# FRAM_with_level_converter_integrated.net
KiCad netlist of a schematic drawn in EAGLE
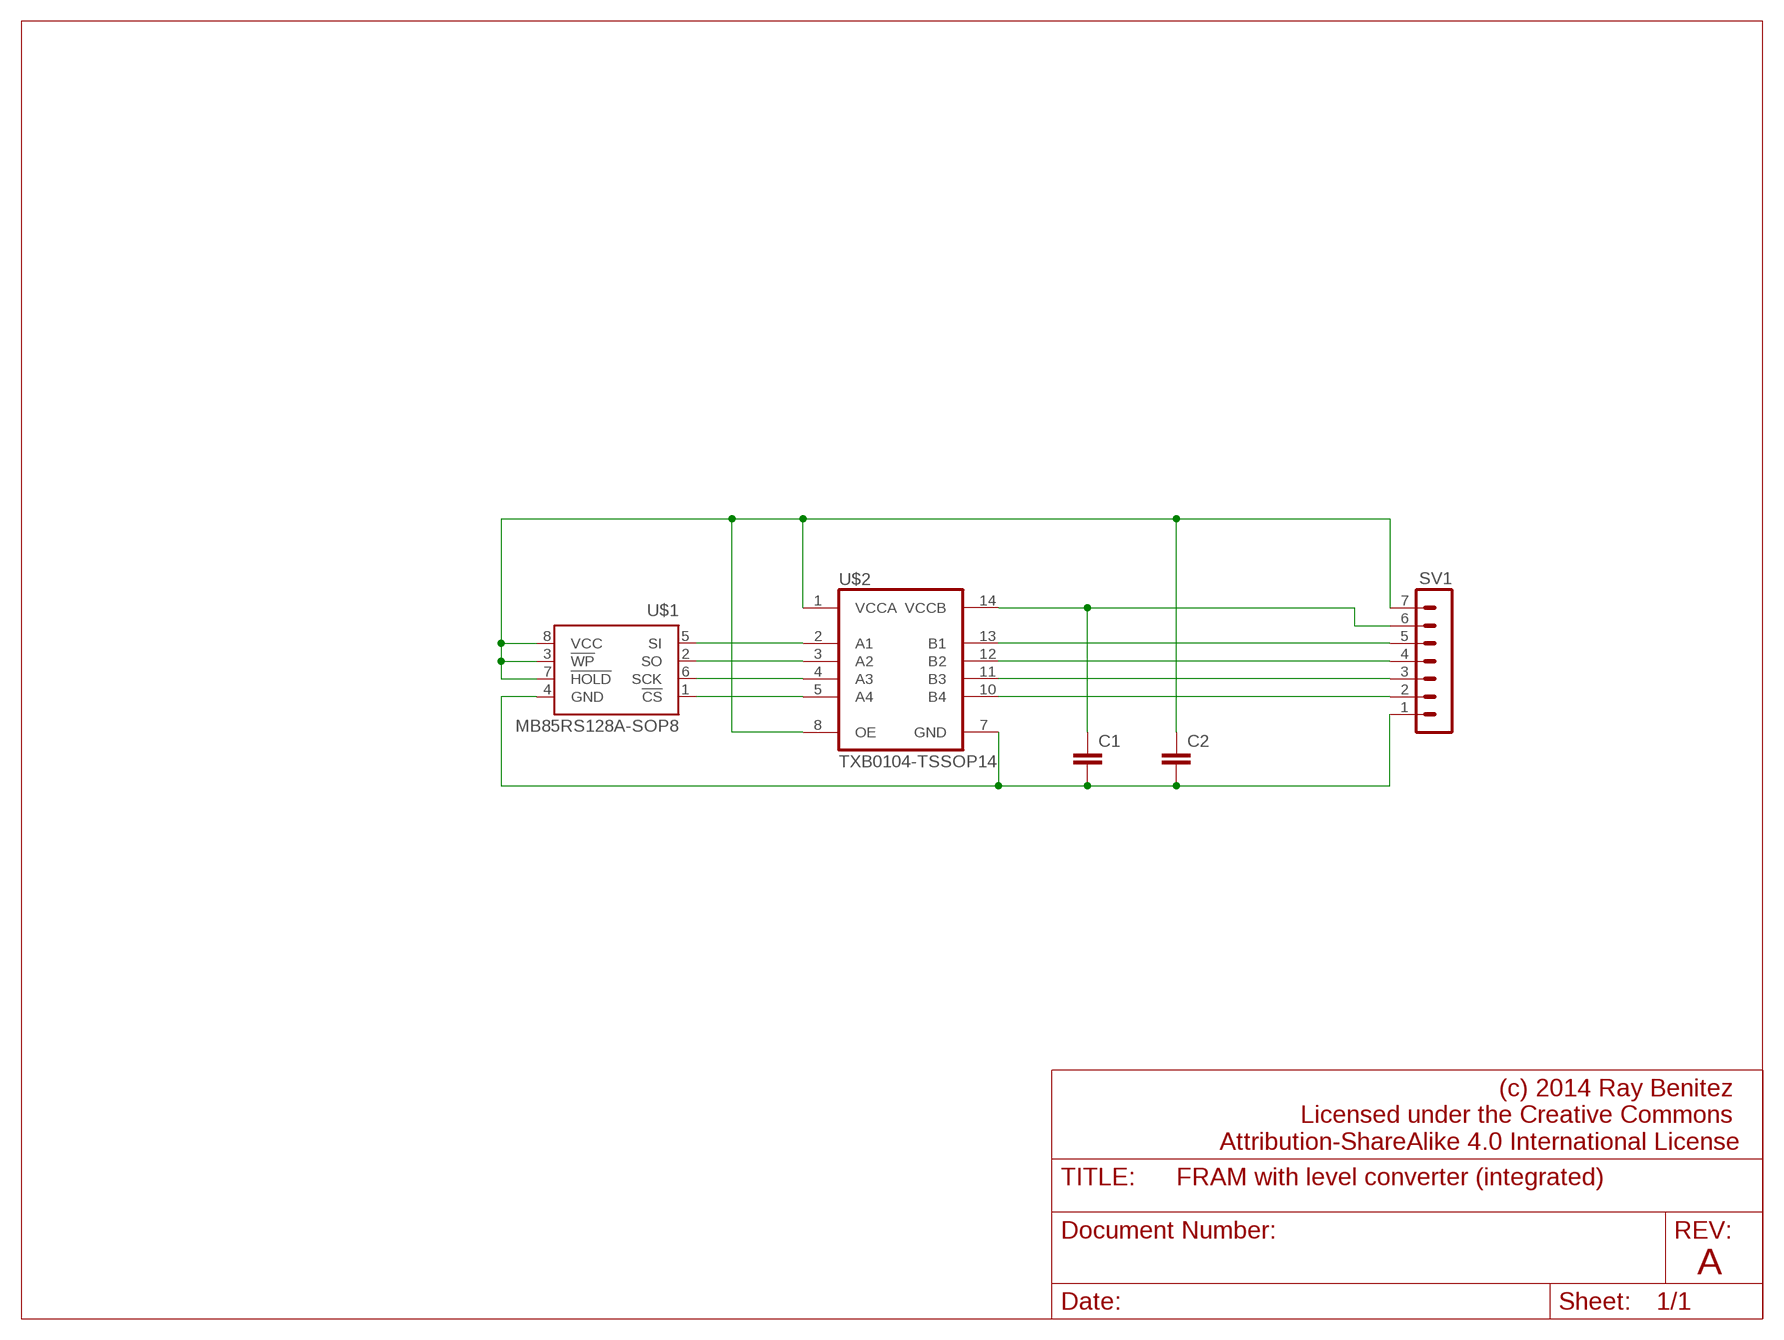
[diagram p0: schematic, sheet 1]

(export (version "E")
  (design (tool "Eeschema 10.0.6"))
  (components
    (comp (ref "C1")
      (value "C-EUC0805")
      (footprint "eagle-import:C0805")
      (libsource (lib "eagle-import") (part "C-EUC0805"))
    )
    (comp (ref "C2")
      (value "C-EUC0805")
      (footprint "eagle-import:C0805")
      (libsource (lib "eagle-import") (part "C-EUC0805"))
    )
    (comp (ref "SV1")
      (value "MA07-1")
      (footprint "eagle-import:MA07-1")
      (libsource (lib "eagle-import") (part "MA07-1"))
    )
    (comp (ref "U$1")
      (value "MB85RS128A-SOP8")
      (footprint "eagle-import:SO08")
      (libsource (lib "eagle-import") (part "MB85RS-SOP8128A"))
    )
    (comp (ref "U$2")
      (value "TXB0104-TSSOP14")
      (footprint "eagle-import:TSSOP14")
      (libsource (lib "eagle-import") (part "TXB0104-TSSOP14"))
    )
  )
  (nets
    (net (code "1") (name "Net-(U$1-GND)") (class "Default")
      (node (ref "C1") (pin "2") (pinfunction "2_2") (pintype "passive"))
      (node (ref "C2") (pin "2") (pinfunction "2_2") (pintype "passive"))
      (node (ref "SV1") (pin "1") (pinfunction "1_1") (pintype "passive"))
      (node (ref "U$1") (pin "4") (pinfunction "GND_4") (pintype "power_in"))
      (node (ref "U$2") (pin "7") (pinfunction "GND_7") (pintype "power_in"))
    )
    (net (code "2") (name "Net-(U$1-SCK)") (class "Default")
      (node (ref "U$1") (pin "6") (pinfunction "SCK_6") (pintype "input"))
      (node (ref "U$2") (pin "4") (pinfunction "A3_4") (pintype "tri_state"))
    )
    (net (code "3") (name "Net-(U$1-SI)") (class "Default")
      (node (ref "U$1") (pin "5") (pinfunction "SI_5") (pintype "input"))
      (node (ref "U$2") (pin "2") (pinfunction "A1_2") (pintype "tri_state"))
    )
    (net (code "4") (name "Net-(U$1-SO)") (class "Default")
      (node (ref "U$1") (pin "2") (pinfunction "SO_2") (pintype "output"))
      (node (ref "U$2") (pin "3") (pinfunction "A2_3") (pintype "tri_state"))
    )
    (net (code "5") (name "Net-(U$1-VCC)") (class "Default")
      (node (ref "C2") (pin "1") (pinfunction "1_1") (pintype "passive"))
      (node (ref "SV1") (pin "7") (pinfunction "7_7") (pintype "passive"))
      (node (ref "U$1") (pin "3") (pinfunction "~{WP}_3") (pintype "input"))
      (node (ref "U$1") (pin "7") (pinfunction "~{HOLD}_7") (pintype "input"))
      (node (ref "U$1") (pin "8") (pinfunction "VCC_8") (pintype "power_in"))
      (node (ref "U$2") (pin "1") (pinfunction "VCCA_1") (pintype "power_in"))
      (node (ref "U$2") (pin "8") (pinfunction "OE_8") (pintype "input"))
    )
    (net (code "6") (name "Net-(U$1-~{CS})") (class "Default")
      (node (ref "U$1") (pin "1") (pinfunction "~{CS}_1") (pintype "input"))
      (node (ref "U$2") (pin "5") (pinfunction "A4_5") (pintype "tri_state"))
    )
    (net (code "7") (name "Net-(U$2-B1)") (class "Default")
      (node (ref "SV1") (pin "5") (pinfunction "5_5") (pintype "passive"))
      (node (ref "U$2") (pin "13") (pinfunction "B1_13") (pintype "tri_state"))
    )
    (net (code "8") (name "Net-(U$2-B2)") (class "Default")
      (node (ref "SV1") (pin "4") (pinfunction "4_4") (pintype "passive"))
      (node (ref "U$2") (pin "12") (pinfunction "B2_12") (pintype "tri_state"))
    )
    (net (code "9") (name "Net-(U$2-B3)") (class "Default")
      (node (ref "SV1") (pin "3") (pinfunction "3_3") (pintype "passive"))
      (node (ref "U$2") (pin "11") (pinfunction "B3_11") (pintype "tri_state"))
    )
    (net (code "10") (name "Net-(U$2-B4)") (class "Default")
      (node (ref "SV1") (pin "2") (pinfunction "2_2") (pintype "passive"))
      (node (ref "U$2") (pin "10") (pinfunction "B4_10") (pintype "tri_state"))
    )
    (net (code "11") (name "Net-(U$2-VCCB)") (class "Default")
      (node (ref "C1") (pin "1") (pinfunction "1_1") (pintype "passive"))
      (node (ref "SV1") (pin "6") (pinfunction "6_6") (pintype "passive"))
      (node (ref "U$2") (pin "14") (pinfunction "VCCB_14") (pintype "power_in"))
    )
  )
)
